# rotary-encoder-breakout-mk-1_0.net
KiCad netlist of a schematic drawn in EAGLE
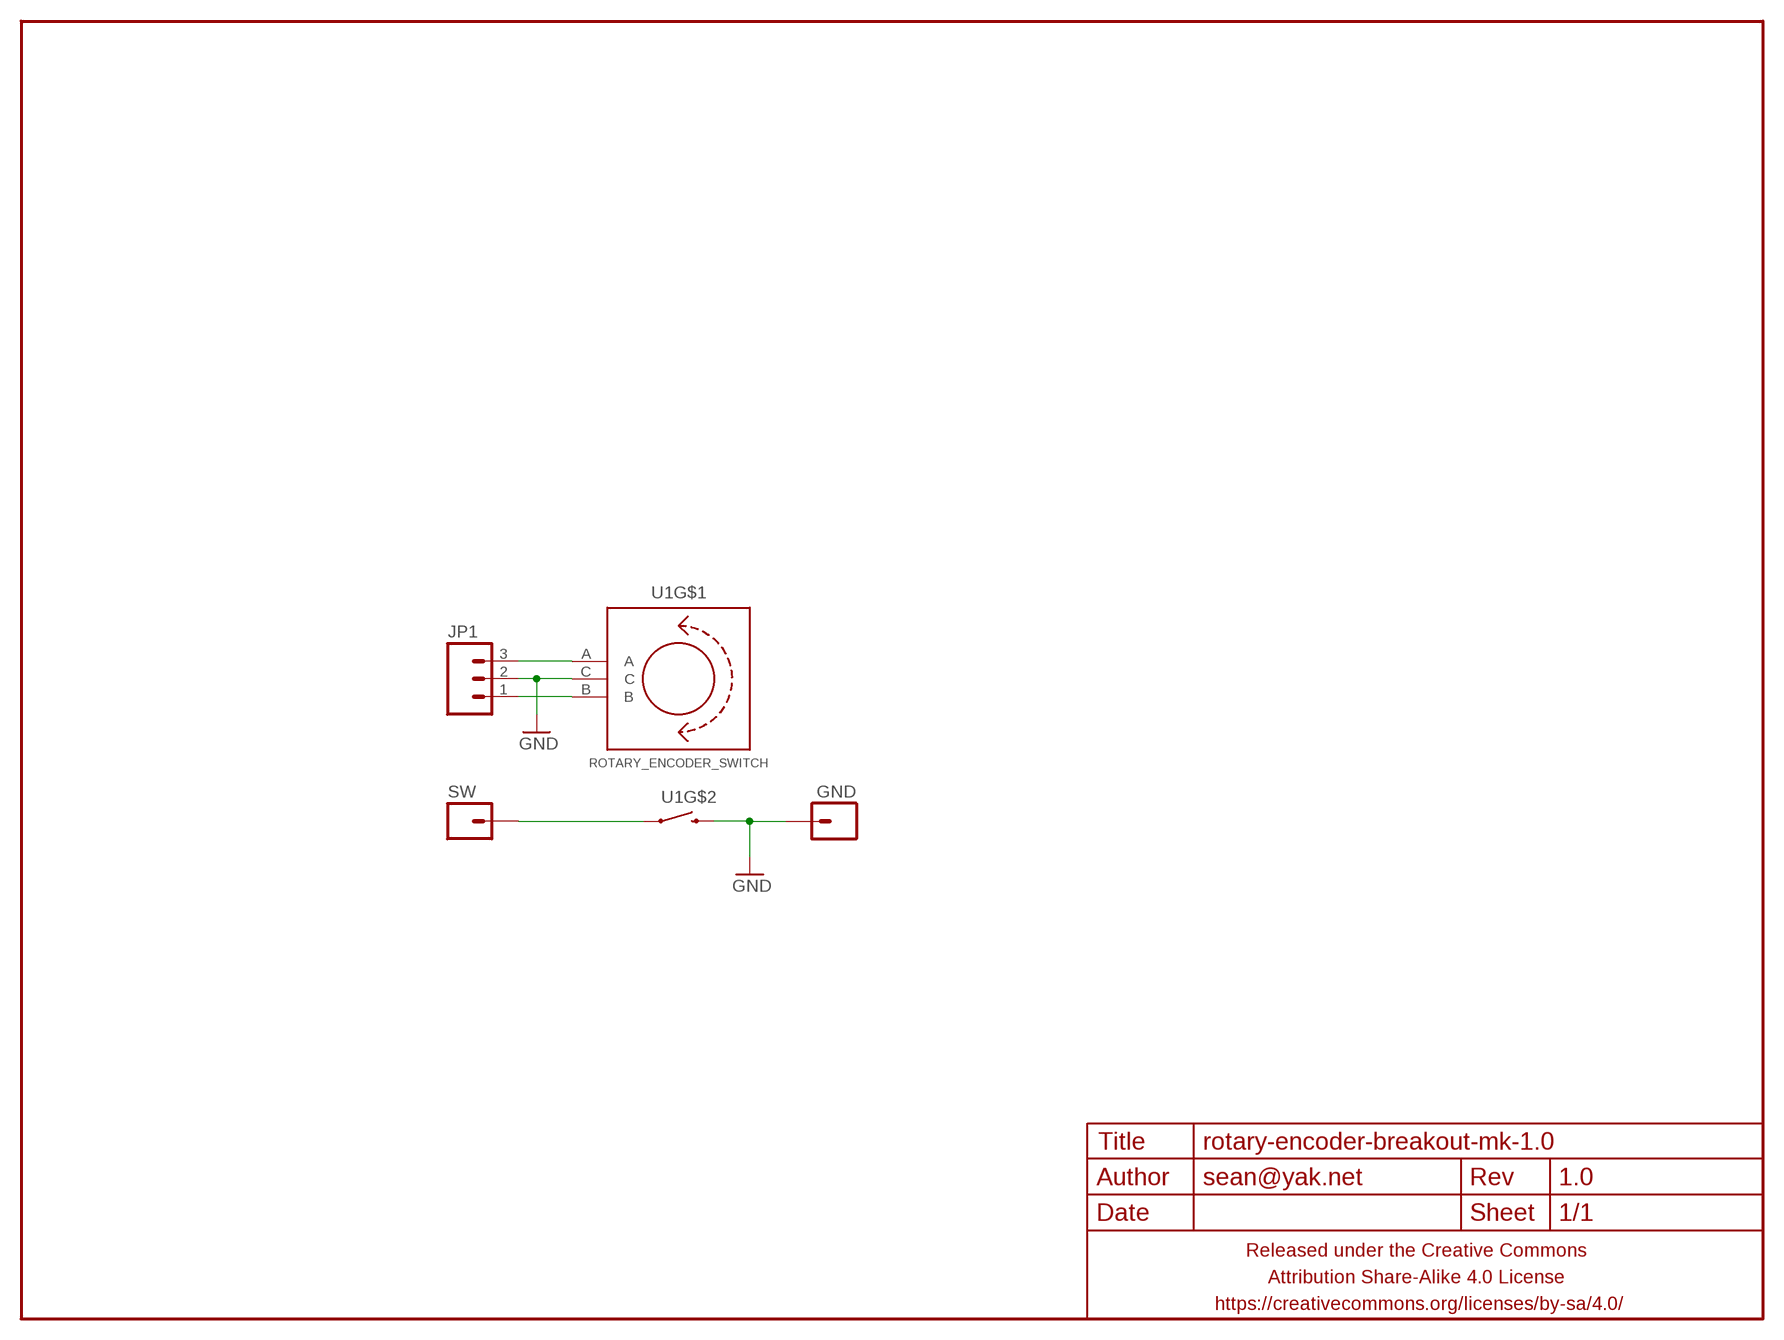
[diagram p0: schematic, sheet 1]

(export (version "E")
  (design (tool "Eeschema 10.0.6"))
  (components
    (comp (ref "FRAME1")
      (value "FRAME-LETTERNO_PACKAGE")
      (footprint "eagle-import:DUMMY")
      (fields (field (name "DESIGNER") "sean@yak.net") (field (name "VERSION") "1.0"))
      (libsource (lib "eagle-import") (part "FRAME-LETTERNO_PACKAGE"))
    )
    (comp (ref "GND")
      (value "M01PTH")
      (footprint "eagle-import:1X01")
      (libsource (lib "eagle-import") (part "M01PTH"))
    )
    (comp (ref "JP1")
      (value "M03PTH")
      (footprint "eagle-import:1X03")
      (libsource (lib "eagle-import") (part "M03PTH"))
    )
    (comp (ref "SW")
      (value "M01PTH")
      (footprint "eagle-import:1X01")
      (libsource (lib "eagle-import") (part "M01PTH"))
    )
    (comp (ref "U1")
      (value "ROTARY_ENCODER_SWITCH")
      (footprint "eagle-import:ROTARY_ENCODER_SWITCH")
      (libsource (lib "eagle-import") (part "ROTARY_ENCODER_SWITCH"))
    )
  )
  (nets
    (net (code "1") (name "GND") (class "Default")
      (node (ref "GND") (pin "1") (pinfunction "1_1") (pintype "passive"))
      (node (ref "JP1") (pin "2") (pinfunction "2_2") (pintype "passive"))
      (node (ref "U1") (pin "C") (pinfunction "C_C") (pintype "bidirectional"))
      (node (ref "U1") (pin "SW2") (pinfunction "2_SW2") (pintype "passive"))
    )
    (net (code "2") (name "Net-(JP1-Pad1)") (class "Default")
      (node (ref "JP1") (pin "1") (pinfunction "1_1") (pintype "passive"))
      (node (ref "U1") (pin "B") (pinfunction "B_B") (pintype "bidirectional"))
    )
    (net (code "3") (name "Net-(JP1-Pad3)") (class "Default")
      (node (ref "JP1") (pin "3") (pinfunction "3_3") (pintype "passive"))
      (node (ref "U1") (pin "A") (pinfunction "A_A") (pintype "bidirectional"))
    )
    (net (code "4") (name "Net-(U1B-1)") (class "Default")
      (node (ref "SW") (pin "1") (pinfunction "1_1") (pintype "passive"))
      (node (ref "U1") (pin "SW1") (pinfunction "1_SW1") (pintype "passive"))
    )
  )
)
